# X15-Backplane.net
KiCad netlist of a schematic drawn in EAGLE
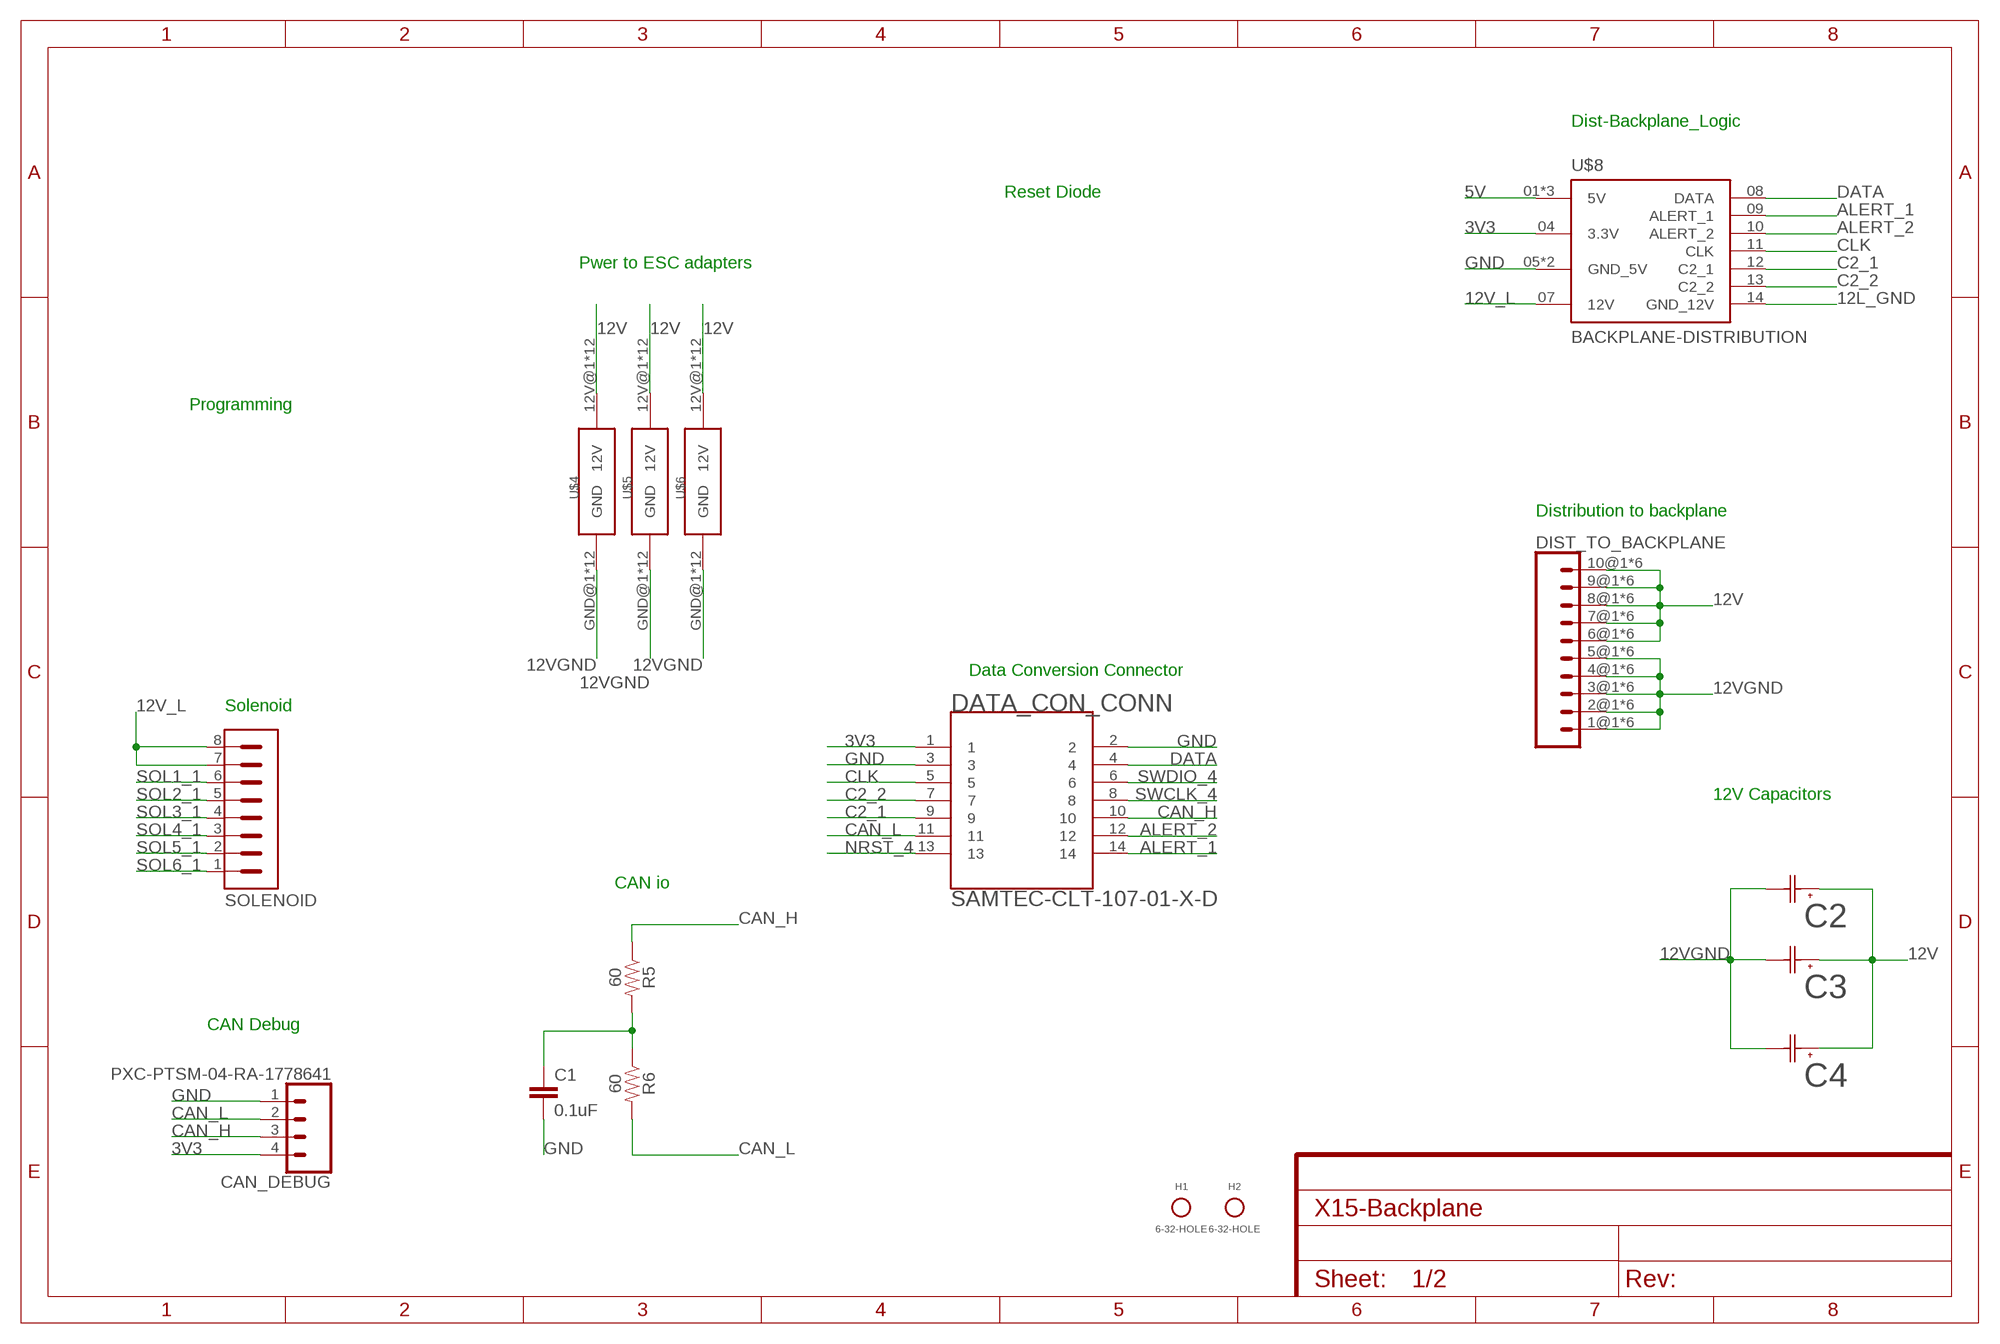
[diagram p0: schematic, sheet 1]
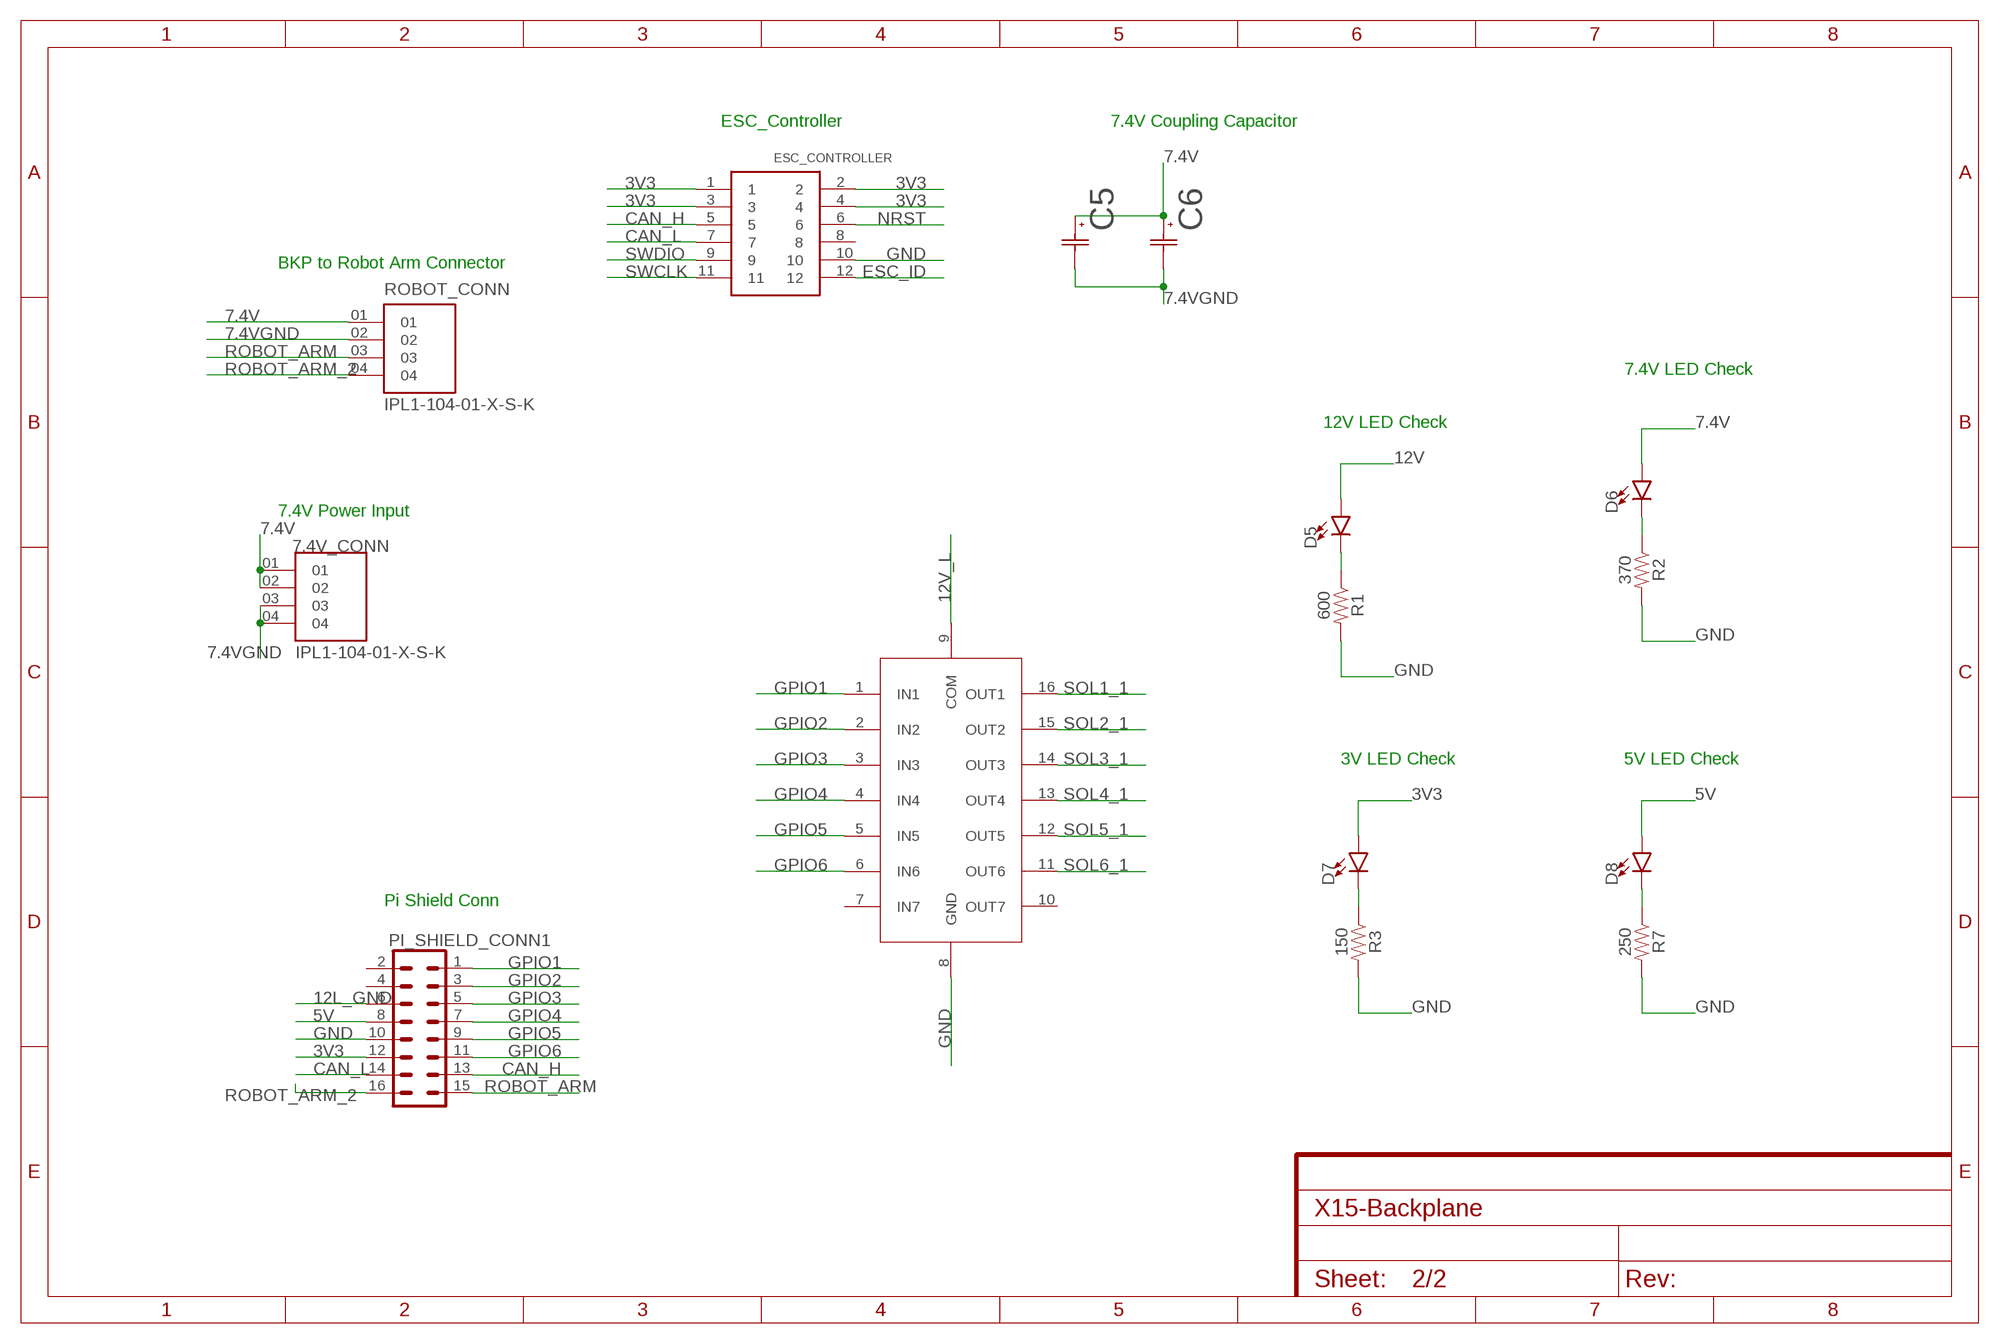
[diagram p1: schematic, sheet 2]

(export (version "E")
  (design (tool "Eeschema 10.0.6"))
  (components
    (comp (ref "7.4V_CONN")
      (value "IPL1-104-01-X-S-K")
      (footprint "eagle-import:SAMTEC_IPL1-104-01-X-S-K")
      (fields (field (name "MANUFACTURER") "SAMTEC"))
      (libsource (lib "eagle-import") (part "IPL1-104-01-X-S-K"))
    )
    (comp (ref "C5")
      (value "UCV1E561MNL1GSCAP_UCD_8X10_NCH")
      (footprint "eagle-import:CAP_UCD_8X10_NCH")
      (fields
        (field (name "MANUFACTURER_PART_NUMBER") "UCV1E561MNL1GS")
        (field (name "COPYRIGHT") "Copyright (C) 2023 Ultra Librarian. All rights reserved.")
      )
      (libsource (lib "eagle-import") (part "UCV1E561MNL1GSCAP_UCD_8X10_NCH"))
    )
    (comp (ref "C6")
      (value "UCV1E561MNL1GSCAP_UCD_8X10_NCH")
      (footprint "eagle-import:CAP_UCD_8X10_NCH")
      (fields
        (field (name "MANUFACTURER_PART_NUMBER") "UCV1E561MNL1GS")
        (field (name "COPYRIGHT") "Copyright (C) 2023 Ultra Librarian. All rights reserved.")
      )
      (libsource (lib "eagle-import") (part "UCV1E561MNL1GSCAP_UCD_8X10_NCH"))
    )
    (comp (ref "D5")
      (value "LED0603")
      (footprint "eagle-import:LED-0603")
      (libsource (lib "eagle-import") (part "LED0603"))
    )
    (comp (ref "D6")
      (value "LED0603")
      (footprint "eagle-import:LED-0603")
      (libsource (lib "eagle-import") (part "LED0603"))
    )
    (comp (ref "D7")
      (value "LED0603")
      (footprint "eagle-import:LED-0603")
      (libsource (lib "eagle-import") (part "LED0603"))
    )
    (comp (ref "D8")
      (value "LED0603")
      (footprint "eagle-import:LED-0603")
      (libsource (lib "eagle-import") (part "LED0603"))
    )
    (comp (ref "ESC_CONTROLLER")
      (value "BACKPLANE_CONNECTORSBKP")
      (footprint "eagle-import:BACKPLANE_CONNECTORS_BKP")
      (libsource (lib "eagle-import") (part "BACKPLANE_CONNECTORSBKP"))
    )
    (comp (ref "PI_SHIELD_CONN1")
      (value "8X_CONN")
      (footprint "eagle-import:IPL7X2")
      (libsource (lib "eagle-import") (part "8X_CONN"))
    )
    (comp (ref "R1")
      (value "600")
      (footprint "eagle-import:0603")
      (libsource (lib "eagle-import") (part "RESISTOR0603"))
    )
    (comp (ref "R2")
      (value "370")
      (footprint "eagle-import:0603")
      (libsource (lib "eagle-import") (part "RESISTOR0603"))
    )
    (comp (ref "R3")
      (value "150")
      (footprint "eagle-import:0603")
      (libsource (lib "eagle-import") (part "RESISTOR0603"))
    )
    (comp (ref "R7")
      (value "250")
      (footprint "eagle-import:0603")
      (libsource (lib "eagle-import") (part "RESISTOR0603"))
    )
    (comp (ref "ROBOT_CONN")
      (value "IPL1-104-01-X-S-K")
      (footprint "eagle-import:SAMTEC_IPL1-104-01-X-S-K")
      (fields (field (name "MANUFACTURER") "SAMTEC"))
      (libsource (lib "eagle-import") (part "IPL1-104-01-X-S-K"))
    )
    (comp (ref "U1")
      (value "ULN2003AD")
      (footprint "eagle-import:16-SOIC")
      (fields (field (name "MANUFACTURER") "Diodes Inc."))
      (libsource (lib "eagle-import") (part "ULN2003AD"))
    )
    (comp (ref "C1")
      (value "0.1uF")
      (footprint "eagle-import:0603")
      (libsource (lib "eagle-import") (part "0.1UF-0603-100V-10%"))
    )
    (comp (ref "C2")
      (value "UCV1E561MNL1GSCAP_UCD_8X10_NCH")
      (footprint "eagle-import:CAP_UCD_8X10_NCH")
      (fields
        (field (name "MANUFACTURER_PART_NUMBER") "UCV1E561MNL1GS")
        (field (name "COPYRIGHT") "Copyright (C) 2023 Ultra Librarian. All rights reserved.")
      )
      (libsource (lib "eagle-import") (part "UCV1E561MNL1GSCAP_UCD_8X10_NCH"))
    )
    (comp (ref "C3")
      (value "UCV1E561MNL1GSCAP_UCD_8X10_NCH")
      (footprint "eagle-import:CAP_UCD_8X10_NCH")
      (fields
        (field (name "MANUFACTURER_PART_NUMBER") "UCV1E561MNL1GS")
        (field (name "COPYRIGHT") "Copyright (C) 2023 Ultra Librarian. All rights reserved.")
      )
      (libsource (lib "eagle-import") (part "UCV1E561MNL1GSCAP_UCD_8X10_NCH"))
    )
    (comp (ref "C4")
      (value "UCV1E561MNL1GSCAP_UCD_8X10_NCH")
      (footprint "eagle-import:CAP_UCD_8X10_NCH")
      (fields
        (field (name "MANUFACTURER_PART_NUMBER") "UCV1E561MNL1GS")
        (field (name "COPYRIGHT") "Copyright (C) 2023 Ultra Librarian. All rights reserved.")
      )
      (libsource (lib "eagle-import") (part "UCV1E561MNL1GSCAP_UCD_8X10_NCH"))
    )
    (comp (ref "CAN_DEBUG")
      (value "PXC-PTSM-04-RA-1778641")
      (footprint "eagle-import:PXC-PTSM-04-RA-1778641")
      (libsource (lib "eagle-import") (part "PXC-PTSM-04-RA-1778641"))
    )
    (comp (ref "DATA_CON_CONN")
      (value "BACKPLANE->DATACONV")
      (footprint "eagle-import:SAMTEC-CLT-107-01-X-D-BACKPLANE")
      (libsource (lib "eagle-import") (part "BACKPLANE-{gt}DATACONV"))
    )
    (comp (ref "DIST_TO_BACKPLANE")
      (value "MPPT-10-01-01-L-RA-SD")
      (footprint "eagle-import:MPPT-10-01-01-L-RA-SD")
      (libsource (lib "eagle-import") (part "MPPT-10-01-01-L-RA-SD"))
    )
    (comp (ref "H1")
      (value "6-32-HOLE")
      (footprint "eagle-import:6-32-HOLE")
      (libsource (lib "eagle-import") (part "6-32-HOLE"))
    )
    (comp (ref "H2")
      (value "6-32-HOLE")
      (footprint "eagle-import:6-32-HOLE")
      (libsource (lib "eagle-import") (part "6-32-HOLE"))
    )
    (comp (ref "R5")
      (value "60")
      (footprint "eagle-import:0603")
      (libsource (lib "eagle-import") (part "RESISTOR0603"))
    )
    (comp (ref "R6")
      (value "60")
      (footprint "eagle-import:0603")
      (libsource (lib "eagle-import") (part "RESISTOR0603"))
    )
    (comp (ref "SOLENOID")
      (value "PXC-8-RA-1778683")
      (footprint "eagle-import:PXC-8-RA-1778683")
      (fields (field (name "SPICEPREFIX") "X"))
      (libsource (lib "eagle-import") (part "PXC-8-RA-1778683"))
    )
    (comp (ref "U$4")
      (value "BACKPLANE_ESC_ADAPTER_PWRBKP")
      (footprint "eagle-import:BACKPLANE_ESC_ADAPTER_BKP_PWR")
      (libsource (lib "eagle-import") (part "BACKPLANE_ESC_ADAPTER_PWRBKP"))
    )
    (comp (ref "U$5")
      (value "BACKPLANE_ESC_ADAPTER_PWRBKP")
      (footprint "eagle-import:BACKPLANE_ESC_ADAPTER_BKP_PWR")
      (libsource (lib "eagle-import") (part "BACKPLANE_ESC_ADAPTER_PWRBKP"))
    )
    (comp (ref "U$6")
      (value "BACKPLANE_ESC_ADAPTER_PWRBKP")
      (footprint "eagle-import:BACKPLANE_ESC_ADAPTER_BKP_PWR")
      (libsource (lib "eagle-import") (part "BACKPLANE_ESC_ADAPTER_PWRBKP"))
    )
    (comp (ref "U$8")
      (value "BACKPLANE-DISTRIBUTION")
      (footprint "eagle-import:SAMTEC_IPL1-107-01-X-D-K(B-D)")
      (libsource (lib "eagle-import") (part "BACKPLANE-DISTRIBUTION"))
    )
  )
  (nets
    (net (code "1") (name "3V3") (class "Default")
      (node (ref "CAN_DEBUG") (pin "4") (pinfunction "4_4") (pintype "passive"))
      (node (ref "D7") (pin "A") (pinfunction "A_A") (pintype "passive"))
      (node (ref "DATA_CON_CONN") (pin "1") (pinfunction "1_1") (pintype "passive"))
      (node (ref "ESC_CONTROLLER") (pin "1") (pinfunction "1_1") (pintype "passive"))
      (node (ref "ESC_CONTROLLER") (pin "2") (pinfunction "2_2") (pintype "passive"))
      (node (ref "ESC_CONTROLLER") (pin "3") (pinfunction "3_3") (pintype "passive"))
      (node (ref "ESC_CONTROLLER") (pin "4") (pinfunction "4_4") (pintype "passive"))
      (node (ref "PI_SHIELD_CONN1") (pin "12") (pinfunction "23_12") (pintype "passive"))
      (node (ref "U$8") (pin "04") (pinfunction "3.3V_04") (pintype "passive"))
    )
    (net (code "2") (name "5V") (class "Default")
      (node (ref "D8") (pin "A") (pinfunction "A_A") (pintype "passive"))
      (node (ref "PI_SHIELD_CONN1") (pin "8") (pinfunction "19_8") (pintype "passive"))
      (node (ref "U$8") (pin "01") (pinfunction "5V_01") (pintype "passive"))
      (node (ref "U$8") (pin "02") (pinfunction "5V_02") (pintype "passive"))
      (node (ref "U$8") (pin "03") (pinfunction "5V_03") (pintype "passive"))
    )
    (net (code "3") (name "7.4V") (class "Default")
      (node (ref "7.4V_CONN") (pin "01") (pinfunction "01_01") (pintype "passive"))
      (node (ref "7.4V_CONN") (pin "02") (pinfunction "02_02") (pintype "passive"))
      (node (ref "C5") (pin "1") (pinfunction "1_1") (pintype "passive"))
      (node (ref "C6") (pin "1") (pinfunction "1_1") (pintype "passive"))
      (node (ref "D6") (pin "A") (pinfunction "A_A") (pintype "passive"))
      (node (ref "ROBOT_CONN") (pin "01") (pinfunction "01_01") (pintype "passive"))
    )
    (net (code "4") (name "7.4VGND") (class "Default")
      (node (ref "7.4V_CONN") (pin "03") (pinfunction "03_03") (pintype "passive"))
      (node (ref "7.4V_CONN") (pin "04") (pinfunction "04_04") (pintype "passive"))
      (node (ref "C5") (pin "2") (pinfunction "2_2") (pintype "passive"))
      (node (ref "C6") (pin "2") (pinfunction "2_2") (pintype "passive"))
      (node (ref "ROBOT_CONN") (pin "02") (pinfunction "02_02") (pintype "passive"))
    )
    (net (code "5") (name "12L_GND") (class "Default")
      (node (ref "PI_SHIELD_CONN1") (pin "6") (pinfunction "17_6") (pintype "passive"))
      (node (ref "U$8") (pin "14") (pinfunction "GND_12V_14") (pintype "passive"))
    )
    (net (code "6") (name "12V") (class "Default")
      (node (ref "C2") (pin "1") (pinfunction "1_1") (pintype "passive"))
      (node (ref "C3") (pin "1") (pinfunction "1_1") (pintype "passive"))
      (node (ref "C4") (pin "1") (pinfunction "1_1") (pintype "passive"))
      (node (ref "D5") (pin "A") (pinfunction "A_A") (pintype "passive"))
      (node (ref "DIST_TO_BACKPLANE") (pin "10@1") (pinfunction "10_10@1") (pintype "passive"))
      (node (ref "DIST_TO_BACKPLANE") (pin "10@2") (pinfunction "10_10@2") (pintype "passive"))
      (node (ref "DIST_TO_BACKPLANE") (pin "10@3") (pinfunction "10_10@3") (pintype "passive"))
      (node (ref "DIST_TO_BACKPLANE") (pin "10@4") (pinfunction "10_10@4") (pintype "passive"))
      (node (ref "DIST_TO_BACKPLANE") (pin "10@5") (pinfunction "10_10@5") (pintype "passive"))
      (node (ref "DIST_TO_BACKPLANE") (pin "10@6") (pinfunction "10_10@6") (pintype "passive"))
      (node (ref "DIST_TO_BACKPLANE") (pin "6@1") (pinfunction "6_6@1") (pintype "passive"))
      (node (ref "DIST_TO_BACKPLANE") (pin "6@2") (pinfunction "6_6@2") (pintype "passive"))
      (node (ref "DIST_TO_BACKPLANE") (pin "6@3") (pinfunction "6_6@3") (pintype "passive"))
      (node (ref "DIST_TO_BACKPLANE") (pin "6@4") (pinfunction "6_6@4") (pintype "passive"))
      (node (ref "DIST_TO_BACKPLANE") (pin "6@5") (pinfunction "6_6@5") (pintype "passive"))
      (node (ref "DIST_TO_BACKPLANE") (pin "6@6") (pinfunction "6_6@6") (pintype "passive"))
      (node (ref "DIST_TO_BACKPLANE") (pin "7@1") (pinfunction "7_7@1") (pintype "passive"))
      (node (ref "DIST_TO_BACKPLANE") (pin "7@2") (pinfunction "7_7@2") (pintype "passive"))
      (node (ref "DIST_TO_BACKPLANE") (pin "7@3") (pinfunction "7_7@3") (pintype "passive"))
      (node (ref "DIST_TO_BACKPLANE") (pin "7@4") (pinfunction "7_7@4") (pintype "passive"))
      (node (ref "DIST_TO_BACKPLANE") (pin "7@5") (pinfunction "7_7@5") (pintype "passive"))
      (node (ref "DIST_TO_BACKPLANE") (pin "7@6") (pinfunction "7_7@6") (pintype "passive"))
      (node (ref "DIST_TO_BACKPLANE") (pin "8@1") (pinfunction "8_8@1") (pintype "passive"))
      (node (ref "DIST_TO_BACKPLANE") (pin "8@2") (pinfunction "8_8@2") (pintype "passive"))
      (node (ref "DIST_TO_BACKPLANE") (pin "8@3") (pinfunction "8_8@3") (pintype "passive"))
      (node (ref "DIST_TO_BACKPLANE") (pin "8@4") (pinfunction "8_8@4") (pintype "passive"))
      (node (ref "DIST_TO_BACKPLANE") (pin "8@5") (pinfunction "8_8@5") (pintype "passive"))
      (node (ref "DIST_TO_BACKPLANE") (pin "8@6") (pinfunction "8_8@6") (pintype "passive"))
      (node (ref "DIST_TO_BACKPLANE") (pin "9@1") (pinfunction "9_9@1") (pintype "passive"))
      (node (ref "DIST_TO_BACKPLANE") (pin "9@2") (pinfunction "9_9@2") (pintype "passive"))
      (node (ref "DIST_TO_BACKPLANE") (pin "9@3") (pinfunction "9_9@3") (pintype "passive"))
      (node (ref "DIST_TO_BACKPLANE") (pin "9@4") (pinfunction "9_9@4") (pintype "passive"))
      (node (ref "DIST_TO_BACKPLANE") (pin "9@5") (pinfunction "9_9@5") (pintype "passive"))
      (node (ref "DIST_TO_BACKPLANE") (pin "9@6") (pinfunction "9_9@6") (pintype "passive"))
      (node (ref "U$4") (pin "12V@1") (pinfunction "12V_12V@1") (pintype "bidirectional"))
      (node (ref "U$4") (pin "12V@10") (pinfunction "12V_12V@10") (pintype "bidirectional"))
      (node (ref "U$4") (pin "12V@11") (pinfunction "12V_12V@11") (pintype "bidirectional"))
      (node (ref "U$4") (pin "12V@12") (pinfunction "12V_12V@12") (pintype "bidirectional"))
      (node (ref "U$4") (pin "12V@2") (pinfunction "12V_12V@2") (pintype "bidirectional"))
      (node (ref "U$4") (pin "12V@3") (pinfunction "12V_12V@3") (pintype "bidirectional"))
      (node (ref "U$4") (pin "12V@4") (pinfunction "12V_12V@4") (pintype "bidirectional"))
      (node (ref "U$4") (pin "12V@5") (pinfunction "12V_12V@5") (pintype "bidirectional"))
      (node (ref "U$4") (pin "12V@6") (pinfunction "12V_12V@6") (pintype "bidirectional"))
      (node (ref "U$4") (pin "12V@7") (pinfunction "12V_12V@7") (pintype "bidirectional"))
      (node (ref "U$4") (pin "12V@8") (pinfunction "12V_12V@8") (pintype "bidirectional"))
      (node (ref "U$4") (pin "12V@9") (pinfunction "12V_12V@9") (pintype "bidirectional"))
      (node (ref "U$5") (pin "12V@1") (pinfunction "12V_12V@1") (pintype "bidirectional"))
      (node (ref "U$5") (pin "12V@10") (pinfunction "12V_12V@10") (pintype "bidirectional"))
      (node (ref "U$5") (pin "12V@11") (pinfunction "12V_12V@11") (pintype "bidirectional"))
      (node (ref "U$5") (pin "12V@12") (pinfunction "12V_12V@12") (pintype "bidirectional"))
      (node (ref "U$5") (pin "12V@2") (pinfunction "12V_12V@2") (pintype "bidirectional"))
      (node (ref "U$5") (pin "12V@3") (pinfunction "12V_12V@3") (pintype "bidirectional"))
      (node (ref "U$5") (pin "12V@4") (pinfunction "12V_12V@4") (pintype "bidirectional"))
      (node (ref "U$5") (pin "12V@5") (pinfunction "12V_12V@5") (pintype "bidirectional"))
      (node (ref "U$5") (pin "12V@6") (pinfunction "12V_12V@6") (pintype "bidirectional"))
      (node (ref "U$5") (pin "12V@7") (pinfunction "12V_12V@7") (pintype "bidirectional"))
      (node (ref "U$5") (pin "12V@8") (pinfunction "12V_12V@8") (pintype "bidirectional"))
      (node (ref "U$5") (pin "12V@9") (pinfunction "12V_12V@9") (pintype "bidirectional"))
      (node (ref "U$6") (pin "12V@1") (pinfunction "12V_12V@1") (pintype "bidirectional"))
      (node (ref "U$6") (pin "12V@10") (pinfunction "12V_12V@10") (pintype "bidirectional"))
      (node (ref "U$6") (pin "12V@11") (pinfunction "12V_12V@11") (pintype "bidirectional"))
      (node (ref "U$6") (pin "12V@12") (pinfunction "12V_12V@12") (pintype "bidirectional"))
      (node (ref "U$6") (pin "12V@2") (pinfunction "12V_12V@2") (pintype "bidirectional"))
      (node (ref "U$6") (pin "12V@3") (pinfunction "12V_12V@3") (pintype "bidirectional"))
      (node (ref "U$6") (pin "12V@4") (pinfunction "12V_12V@4") (pintype "bidirectional"))
      (node (ref "U$6") (pin "12V@5") (pinfunction "12V_12V@5") (pintype "bidirectional"))
      (node (ref "U$6") (pin "12V@6") (pinfunction "12V_12V@6") (pintype "bidirectional"))
      (node (ref "U$6") (pin "12V@7") (pinfunction "12V_12V@7") (pintype "bidirectional"))
      (node (ref "U$6") (pin "12V@8") (pinfunction "12V_12V@8") (pintype "bidirectional"))
      (node (ref "U$6") (pin "12V@9") (pinfunction "12V_12V@9") (pintype "bidirectional"))
    )
    (net (code "7") (name "12VGND") (class "Default")
      (node (ref "C2") (pin "2") (pinfunction "2_2") (pintype "passive"))
      (node (ref "C3") (pin "2") (pinfunction "2_2") (pintype "passive"))
      (node (ref "C4") (pin "2") (pinfunction "2_2") (pintype "passive"))
      (node (ref "DIST_TO_BACKPLANE") (pin "1@1") (pinfunction "1_1@1") (pintype "passive"))
      (node (ref "DIST_TO_BACKPLANE") (pin "1@2") (pinfunction "1_1@2") (pintype "passive"))
      (node (ref "DIST_TO_BACKPLANE") (pin "1@3") (pinfunction "1_1@3") (pintype "passive"))
      (node (ref "DIST_TO_BACKPLANE") (pin "1@4") (pinfunction "1_1@4") (pintype "passive"))
      (node (ref "DIST_TO_BACKPLANE") (pin "1@5") (pinfunction "1_1@5") (pintype "passive"))
      (node (ref "DIST_TO_BACKPLANE") (pin "1@6") (pinfunction "1_1@6") (pintype "passive"))
      (node (ref "DIST_TO_BACKPLANE") (pin "2@1") (pinfunction "2_2@1") (pintype "passive"))
      (node (ref "DIST_TO_BACKPLANE") (pin "2@2") (pinfunction "2_2@2") (pintype "passive"))
      (node (ref "DIST_TO_BACKPLANE") (pin "2@3") (pinfunction "2_2@3") (pintype "passive"))
      (node (ref "DIST_TO_BACKPLANE") (pin "2@4") (pinfunction "2_2@4") (pintype "passive"))
      (node (ref "DIST_TO_BACKPLANE") (pin "2@5") (pinfunction "2_2@5") (pintype "passive"))
      (node (ref "DIST_TO_BACKPLANE") (pin "2@6") (pinfunction "2_2@6") (pintype "passive"))
      (node (ref "DIST_TO_BACKPLANE") (pin "3@1") (pinfunction "3_3@1") (pintype "passive"))
      (node (ref "DIST_TO_BACKPLANE") (pin "3@2") (pinfunction "3_3@2") (pintype "passive"))
      (node (ref "DIST_TO_BACKPLANE") (pin "3@3") (pinfunction "3_3@3") (pintype "passive"))
      (node (ref "DIST_TO_BACKPLANE") (pin "3@4") (pinfunction "3_3@4") (pintype "passive"))
      (node (ref "DIST_TO_BACKPLANE") (pin "3@5") (pinfunction "3_3@5") (pintype "passive"))
      (node (ref "DIST_TO_BACKPLANE") (pin "3@6") (pinfunction "3_3@6") (pintype "passive"))
      (node (ref "DIST_TO_BACKPLANE") (pin "4@1") (pinfunction "4_4@1") (pintype "passive"))
      (node (ref "DIST_TO_BACKPLANE") (pin "4@2") (pinfunction "4_4@2") (pintype "passive"))
      (node (ref "DIST_TO_BACKPLANE") (pin "4@3") (pinfunction "4_4@3") (pintype "passive"))
      (node (ref "DIST_TO_BACKPLANE") (pin "4@4") (pinfunction "4_4@4") (pintype "passive"))
      (node (ref "DIST_TO_BACKPLANE") (pin "4@5") (pinfunction "4_4@5") (pintype "passive"))
      (node (ref "DIST_TO_BACKPLANE") (pin "4@6") (pinfunction "4_4@6") (pintype "passive"))
      (node (ref "DIST_TO_BACKPLANE") (pin "5@1") (pinfunction "5_5@1") (pintype "passive"))
      (node (ref "DIST_TO_BACKPLANE") (pin "5@2") (pinfunction "5_5@2") (pintype "passive"))
      (node (ref "DIST_TO_BACKPLANE") (pin "5@3") (pinfunction "5_5@3") (pintype "passive"))
      (node (ref "DIST_TO_BACKPLANE") (pin "5@4") (pinfunction "5_5@4") (pintype "passive"))
      (node (ref "DIST_TO_BACKPLANE") (pin "5@5") (pinfunction "5_5@5") (pintype "passive"))
      (node (ref "DIST_TO_BACKPLANE") (pin "5@6") (pinfunction "5_5@6") (pintype "passive"))
      (node (ref "U$4") (pin "GND@1") (pinfunction "GND_GND@1") (pintype "bidirectional"))
      (node (ref "U$4") (pin "GND@10") (pinfunction "GND_GND@10") (pintype "bidirectional"))
      (node (ref "U$4") (pin "GND@11") (pinfunction "GND_GND@11") (pintype "bidirectional"))
      (node (ref "U$4") (pin "GND@12") (pinfunction "GND_GND@12") (pintype "bidirectional"))
      (node (ref "U$4") (pin "GND@2") (pinfunction "GND_GND@2") (pintype "bidirectional"))
      (node (ref "U$4") (pin "GND@3") (pinfunction "GND_GND@3") (pintype "bidirectional"))
      (node (ref "U$4") (pin "GND@4") (pinfunction "GND_GND@4") (pintype "bidirectional"))
      (node (ref "U$4") (pin "GND@5") (pinfunction "GND_GND@5") (pintype "bidirectional"))
      (node (ref "U$4") (pin "GND@6") (pinfunction "GND_GND@6") (pintype "bidirectional"))
      (node (ref "U$4") (pin "GND@7") (pinfunction "GND_GND@7") (pintype "bidirectional"))
      (node (ref "U$4") (pin "GND@8") (pinfunction "GND_GND@8") (pintype "bidirectional"))
      (node (ref "U$4") (pin "GND@9") (pinfunction "GND_GND@9") (pintype "bidirectional"))
      (node (ref "U$5") (pin "GND@1") (pinfunction "GND_GND@1") (pintype "bidirectional"))
      (node (ref "U$5") (pin "GND@10") (pinfunction "GND_GND@10") (pintype "bidirectional"))
      (node (ref "U$5") (pin "GND@11") (pinfunction "GND_GND@11") (pintype "bidirectional"))
      (node (ref "U$5") (pin "GND@12") (pinfunction "GND_GND@12") (pintype "bidirectional"))
      (node (ref "U$5") (pin "GND@2") (pinfunction "GND_GND@2") (pintype "bidirectional"))
      (node (ref "U$5") (pin "GND@3") (pinfunction "GND_GND@3") (pintype "bidirectional"))
      (node (ref "U$5") (pin "GND@4") (pinfunction "GND_GND@4") (pintype "bidirectional"))
      (node (ref "U$5") (pin "GND@5") (pinfunction "GND_GND@5") (pintype "bidirectional"))
      (node (ref "U$5") (pin "GND@6") (pinfunction "GND_GND@6") (pintype "bidirectional"))
      (node (ref "U$5") (pin "GND@7") (pinfunction "GND_GND@7") (pintype "bidirectional"))
      (node (ref "U$5") (pin "GND@8") (pinfunction "GND_GND@8") (pintype "bidirectional"))
      (node (ref "U$5") (pin "GND@9") (pinfunction "GND_GND@9") (pintype "bidirectional"))
      (node (ref "U$6") (pin "GND@1") (pinfunction "GND_GND@1") (pintype "bidirectional"))
      (node (ref "U$6") (pin "GND@10") (pinfunction "GND_GND@10") (pintype "bidirectional"))
      (node (ref "U$6") (pin "GND@11") (pinfunction "GND_GND@11") (pintype "bidirectional"))
      (node (ref "U$6") (pin "GND@12") (pinfunction "GND_GND@12") (pintype "bidirectional"))
      (node (ref "U$6") (pin "GND@2") (pinfunction "GND_GND@2") (pintype "bidirectional"))
      (node (ref "U$6") (pin "GND@3") (pinfunction "GND_GND@3") (pintype "bidirectional"))
      (node (ref "U$6") (pin "GND@4") (pinfunction "GND_GND@4") (pintype "bidirectional"))
      (node (ref "U$6") (pin "GND@5") (pinfunction "GND_GND@5") (pintype "bidirectional"))
      (node (ref "U$6") (pin "GND@6") (pinfunction "GND_GND@6") (pintype "bidirectional"))
      (node (ref "U$6") (pin "GND@7") (pinfunction "GND_GND@7") (pintype "bidirectional"))
      (node (ref "U$6") (pin "GND@8") (pinfunction "GND_GND@8") (pintype "bidirectional"))
      (node (ref "U$6") (pin "GND@9") (pinfunction "GND_GND@9") (pintype "bidirectional"))
    )
    (net (code "8") (name "12V_L") (class "Default")
      (node (ref "SOLENOID") (pin "7") (pinfunction "7_7") (pintype "passive"))
      (node (ref "SOLENOID") (pin "8") (pinfunction "8_8") (pintype "passive"))
      (node (ref "U$8") (pin "07") (pinfunction "12V_07") (pintype "passive"))
      (node (ref "U1") (pin "9") (pinfunction "COM_9") (pintype "bidirectional"))
    )
    (net (code "9") (name "ALERT_1") (class "Default")
      (node (ref "DATA_CON_CONN") (pin "14") (pinfunction "14_14") (pintype "passive"))
      (node (ref "U$8") (pin "09") (pinfunction "ALERT_1_09") (pintype "passive"))
    )
    (net (code "10") (name "ALERT_2") (class "Default")
      (node (ref "DATA_CON_CONN") (pin "12") (pinfunction "12_12") (pintype "passive"))
      (node (ref "U$8") (pin "10") (pinfunction "ALERT_2_10") (pintype "passive"))
    )
    (net (code "11") (name "C2_1") (class "Default")
      (node (ref "DATA_CON_CONN") (pin "9") (pinfunction "9_9") (pintype "passive"))
      (node (ref "U$8") (pin "12") (pinfunction "C2_1_12") (pintype "passive"))
    )
    (net (code "12") (name "C2_2") (class "Default")
      (node (ref "DATA_CON_CONN") (pin "7") (pinfunction "7_7") (pintype "passive"))
      (node (ref "U$8") (pin "13") (pinfunction "C2_2_13") (pintype "passive"))
    )
    (net (code "13") (name "CAN_H") (class "Default")
      (node (ref "CAN_DEBUG") (pin "3") (pinfunction "3_3") (pintype "passive"))
      (node (ref "DATA_CON_CONN") (pin "10") (pinfunction "10_10") (pintype "passive"))
      (node (ref "ESC_CONTROLLER") (pin "5") (pinfunction "5_5") (pintype "passive"))
      (node (ref "PI_SHIELD_CONN1") (pin "13") (pinfunction "1_13") (pintype "passive"))
      (node (ref "R5") (pin "1") (pinfunction "1_1") (pintype "passive"))
    )
    (net (code "14") (name "CAN_L") (class "Default")
      (node (ref "CAN_DEBUG") (pin "2") (pinfunction "2_2") (pintype "passive"))
      (node (ref "DATA_CON_CONN") (pin "11") (pinfunction "11_11") (pintype "passive"))
      (node (ref "ESC_CONTROLLER") (pin "7") (pinfunction "7_7") (pintype "passive"))
      (node (ref "PI_SHIELD_CONN1") (pin "14") (pinfunction "2_14") (pintype "passive"))
      (node (ref "R6") (pin "2") (pinfunction "2_2") (pintype "passive"))
    )
    (net (code "15") (name "CLK") (class "Default")
      (node (ref "DATA_CON_CONN") (pin "5") (pinfunction "5_5") (pintype "passive"))
      (node (ref "U$8") (pin "11") (pinfunction "CLK_11") (pintype "passive"))
    )
    (net (code "16") (name "DATA") (class "Default")
      (node (ref "DATA_CON_CONN") (pin "4") (pinfunction "4_4") (pintype "passive"))
      (node (ref "U$8") (pin "08") (pinfunction "DATA_08") (pintype "passive"))
    )
    (net (code "17") (name "ESC_ID") (class "Default")
      (node (ref "ESC_CONTROLLER") (pin "12") (pinfunction "12_12") (pintype "passive"))
    )
    (net (code "18") (name "GND") (class "Default")
      (node (ref "C1") (pin "2") (pinfunction "2_2") (pintype "passive"))
      (node (ref "CAN_DEBUG") (pin "1") (pinfunction "1_1") (pintype "passive"))
      (node (ref "DATA_CON_CONN") (pin "2") (pinfunction "2_2") (pintype "passive"))
      (node (ref "DATA_CON_CONN") (pin "3") (pinfunction "3_3") (pintype "passive"))
      (node (ref "ESC_CONTROLLER") (pin "10") (pinfunction "10_10") (pintype "passive"))
      (node (ref "PI_SHIELD_CONN1") (pin "10") (pinfunction "21_10") (pintype "passive"))
      (node (ref "R1") (pin "2") (pinfunction "2_2") (pintype "passive"))
      (node (ref "R2") (pin "2") (pinfunction "2_2") (pintype "passive"))
      (node (ref "R3") (pin "2") (pinfunction "2_2") (pintype "passive"))
      (node (ref "R7") (pin "2") (pinfunction "2_2") (pintype "passive"))
      (node (ref "U$8") (pin "05") (pinfunction "GND_5V_05") (pintype "passive"))
      (node (ref "U$8") (pin "06") (pinfunction "GND_5V_06") (pintype "passive"))
      (node (ref "U1") (pin "8") (pinfunction "GND_8") (pintype "bidirectional"))
    )
    (net (code "19") (name "GPIO1") (class "Default")
      (node (ref "PI_SHIELD_CONN1") (pin "1") (pinfunction "14_1") (pintype "passive"))
      (node (ref "U1") (pin "1") (pinfunction "IN1_1") (pintype "bidirectional"))
    )
    (net (code "20") (name "GPIO2") (class "Default")
      (node (ref "PI_SHIELD_CONN1") (pin "3") (pinfunction "16_3") (pintype "passive"))
      (node (ref "U1") (pin "2") (pinfunction "IN2_2") (pintype "bidirectional"))
    )
    (net (code "21") (name "GPIO3") (class "Default")
      (node (ref "PI_SHIELD_CONN1") (pin "5") (pinfunction "18_5") (pintype "passive"))
      (node (ref "U1") (pin "3") (pinfunction "IN3_3") (pintype "bidirectional"))
    )
    (net (code "22") (name "GPIO4") (class "Default")
      (node (ref "PI_SHIELD_CONN1") (pin "7") (pinfunction "20_7") (pintype "passive"))
      (node (ref "U1") (pin "4") (pinfunction "IN4_4") (pintype "bidirectional"))
    )
    (net (code "23") (name "GPIO5") (class "Default")
      (node (ref "PI_SHIELD_CONN1") (pin "9") (pinfunction "22_9") (pintype "passive"))
      (node (ref "U1") (pin "5") (pinfunction "IN5_5") (pintype "bidirectional"))
    )
    (net (code "24") (name "GPIO6") (class "Default")
      (node (ref "PI_SHIELD_CONN1") (pin "11") (pinfunction "24_11") (pintype "passive"))
      (node (ref "U1") (pin "6") (pinfunction "IN6_6") (pintype "bidirectional"))
    )
    (net (code "25") (name "NRST") (class "Default")
      (node (ref "ESC_CONTROLLER") (pin "6") (pinfunction "6_6") (pintype "passive"))
    )
    (net (code "26") (name "NRST_4") (class "Default")
      (node (ref "DATA_CON_CONN") (pin "13") (pinfunction "13_13") (pintype "passive"))
    )
    (net (code "27") (name "Net-(C1-Pad1)") (class "Default")
      (node (ref "C1") (pin "1") (pinfunction "1_1") (pintype "passive"))
      (node (ref "R5") (pin "2") (pinfunction "2_2") (pintype "passive"))
      (node (ref "R6") (pin "1") (pinfunction "1_1") (pintype "passive"))
    )
    (net (code "28") (name "Net-(D5-PadC)") (class "Default")
      (node (ref "D5") (pin "C") (pinfunction "C_C") (pintype "passive"))
      (node (ref "R1") (pin "1") (pinfunction "1_1") (pintype "passive"))
    )
    (net (code "29") (name "Net-(D6-PadC)") (class "Default")
      (node (ref "D6") (pin "C") (pinfunction "C_C") (pintype "passive"))
      (node (ref "R2") (pin "1") (pinfunction "1_1") (pintype "passive"))
    )
    (net (code "30") (name "Net-(D7-PadC)") (class "Default")
      (node (ref "D7") (pin "C") (pinfunction "C_C") (pintype "passive"))
      (node (ref "R3") (pin "1") (pinfunction "1_1") (pintype "passive"))
    )
    (net (code "31") (name "Net-(D8-PadC)") (class "Default")
      (node (ref "D8") (pin "C") (pinfunction "C_C") (pintype "passive"))
      (node (ref "R7") (pin "1") (pinfunction "1_1") (pintype "passive"))
    )
    (net (code "32") (name "ROBOT_ARM") (class "Default")
      (node (ref "PI_SHIELD_CONN1") (pin "15") (pinfunction "4_15") (pintype "passive"))
      (node (ref "ROBOT_CONN") (pin "03") (pinfunction "03_03") (pintype "passive"))
    )
    (net (code "33") (name "ROBOT_ARM_2") (class "Default")
      (node (ref "PI_SHIELD_CONN1") (pin "16") (pinfunction "3_16") (pintype "passive"))
      (node (ref "ROBOT_CONN") (pin "04") (pinfunction "04_04") (pintype "passive"))
    )
    (net (code "34") (name "SOL1_1") (class "Default")
      (node (ref "SOLENOID") (pin "6") (pinfunction "6_6") (pintype "passive"))
      (node (ref "U1") (pin "16") (pinfunction "OUT1_16") (pintype "bidirectional"))
    )
    (net (code "35") (name "SOL2_1") (class "Default")
      (node (ref "SOLENOID") (pin "5") (pinfunction "5_5") (pintype "passive"))
      (node (ref "U1") (pin "15") (pinfunction "OUT2_15") (pintype "bidirectional"))
    )
    (net (code "36") (name "SOL3_1") (class "Default")
      (node (ref "SOLENOID") (pin "4") (pinfunction "4_4") (pintype "passive"))
      (node (ref "U1") (pin "14") (pinfunction "OUT3_14") (pintype "bidirectional"))
    )
    (net (code "37") (name "SOL4_1") (class "Default")
      (node (ref "SOLENOID") (pin "3") (pinfunction "3_3") (pintype "passive"))
      (node (ref "U1") (pin "13") (pinfunction "OUT4_13") (pintype "bidirectional"))
    )
    (net (code "38") (name "SOL5_1") (class "Default")
      (node (ref "SOLENOID") (pin "2") (pinfunction "2_2") (pintype "passive"))
      (node (ref "U1") (pin "12") (pinfunction "OUT5_12") (pintype "bidirectional"))
    )
    (net (code "39") (name "SOL6_1") (class "Default")
      (node (ref "SOLENOID") (pin "1") (pinfunction "1_1") (pintype "passive"))
      (node (ref "U1") (pin "11") (pinfunction "OUT6_11") (pintype "bidirectional"))
    )
    (net (code "40") (name "SWCLK") (class "Default")
      (node (ref "ESC_CONTROLLER") (pin "11") (pinfunction "11_11") (pintype "passive"))
    )
    (net (code "41") (name "SWCLK_4") (class "Default")
      (node (ref "DATA_CON_CONN") (pin "8") (pinfunction "8_8") (pintype "passive"))
    )
    (net (code "42") (name "SWDIO") (class "Default")
      (node (ref "ESC_CONTROLLER") (pin "9") (pinfunction "9_9") (pintype "passive"))
    )
    (net (code "43") (name "SWDIO_4") (class "Default")
      (node (ref "DATA_CON_CONN") (pin "6") (pinfunction "6_6") (pintype "passive"))
    )
    (net (code "44") (name "unconnected-(ESC_CONTROLLER-Pad8)") (class "Default")
      (node (ref "ESC_CONTROLLER") (pin "8") (pinfunction "8_8") (pintype "passive"))
    )
    (net (code "45") (name "unconnected-(PI_SHIELD_CONN1-13-Pad2)") (class "Default")
      (node (ref "PI_SHIELD_CONN1") (pin "2") (pinfunction "13_2") (pintype "passive"))
    )
    (net (code "46") (name "unconnected-(PI_SHIELD_CONN1-15-Pad4)") (class "Default")
      (node (ref "PI_SHIELD_CONN1") (pin "4") (pinfunction "15_4") (pintype "passive"))
    )
    (net (code "47") (name "unconnected-(U1-IN7-Pad7)") (class "Default")
      (node (ref "U1") (pin "7") (pinfunction "IN7_7") (pintype "bidirectional"))
    )
    (net (code "48") (name "unconnected-(U1-OUT7-Pad10)") (class "Default")
      (node (ref "U1") (pin "10") (pinfunction "OUT7_10") (pintype "bidirectional"))
    )
  )
)
